# 1_Rotary_Encoder_Input_output.net
KiCad netlist of a schematic drawn in Altium Designer
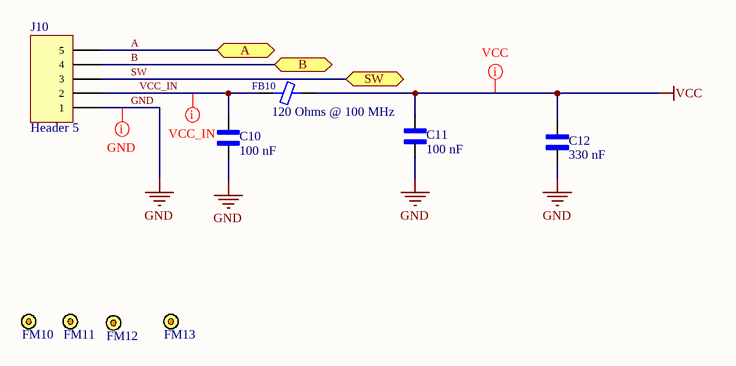
[diagram p0: 1_Rotary_Encoder_Input_output.SchDoc]

(export (version "E")
  (design (tool "Eeschema 10.0.6"))
  (components
    (comp (ref "C10")
      (value "100 nF")
      (footprint "C-0603")
      (description "Ceramic Capacitor 16V 0603 (1608 Metric)")
      (fields (field (name "MP") "C0603C104J4RAC") (field (name "MF") "KEMET"))
      (libsource (lib "Rotary_Encoder") (part "C-0603"))
    )
    (comp (ref "C11")
      (value "100 nF")
      (footprint "C-0603")
      (description "Ceramic Capacitor 16V 0603 (1608 Metric)")
      (fields (field (name "MP") "C0603C104J4RAC") (field (name "MF") "KEMET"))
      (libsource (lib "Rotary_Encoder") (part "C-0603"))
    )
    (comp (ref "C12")
      (value "330 nF")
      (footprint "C-0603")
      (description "Ceramic Capacitor 16V 0603 (1608 Metric)")
      (fields (field (name "MP") "C0603C104J4RAC") (field (name "MF") "KEMET"))
      (libsource (lib "Rotary_Encoder") (part "C-0603"))
    )
    (comp (ref "FB10")
      (value "120 Ohms @ 100 MHz")
      (footprint "FER 0603_1608")
      (description "FERRITE BEAD 120 OHM 0603 1LN")
      (fields
        (field (name "PART NUMBER") "PE-0603PFB121ST")
        (field (name "MANUFACTURER") "Pulse Electronics Network")
      )
      (libsource (lib "Rotary_Encoder") (part "Ferrite Chip"))
    )
    (comp (ref "FM10")
      (value "FM")
      (footprint "Fiducial_Marker_1mm")
      (description "Fiducial Marker")
      (libsource (lib "Rotary_Encoder") (part "Fiducial Marker"))
    )
    (comp (ref "FM11")
      (value "FM")
      (footprint "Fiducial_Marker_1mm")
      (description "Fiducial Marker")
      (libsource (lib "Rotary_Encoder") (part "Fiducial Marker"))
    )
    (comp (ref "FM12")
      (value "FM")
      (footprint "Fiducial_Marker_1mm")
      (description "Fiducial Marker")
      (libsource (lib "Rotary_Encoder") (part "Fiducial Marker"))
    )
    (comp (ref "FM13")
      (value "FM")
      (footprint "Fiducial_Marker_1mm")
      (description "Fiducial Marker")
      (libsource (lib "Rotary_Encoder") (part "Fiducial Marker"))
    )
    (comp (ref "J10")
      (value "Header 5")
      (footprint "HDR1X5")
      (description "Header, 5-Pin")
      (fields (field (name "PUBLISHER") "Altium Limited"))
      (libsource (lib "Rotary_Encoder") (part "Header 5"))
    )
  )
  (nets
    (net (code "1") (name "/A") (class "Default")
      (node (ref "J10") (pin "5") (pinfunction "5_5") (pintype "passive"))
    )
    (net (code "2") (name "/B") (class "Default")
      (node (ref "J10") (pin "4") (pinfunction "4_4") (pintype "passive"))
    )
    (net (code "3") (name "/SW") (class "Default")
      (node (ref "J10") (pin "3") (pinfunction "3_3") (pintype "passive"))
    )
    (net (code "4") (name "/VCC_IN") (class "Default")
      (node (ref "C10") (pin "2") (pinfunction "2_2") (pintype "passive"))
      (node (ref "FB10") (pin "1") (pinfunction "1_1") (pintype "passive"))
      (node (ref "J10") (pin "2") (pinfunction "2_2") (pintype "passive"))
    )
    (net (code "5") (name "GND") (class "Default")
      (node (ref "C10") (pin "1") (pinfunction "1_1") (pintype "passive"))
      (node (ref "C11") (pin "1") (pinfunction "1_1") (pintype "passive"))
      (node (ref "C12") (pin "1") (pinfunction "1_1") (pintype "passive"))
      (node (ref "J10") (pin "1") (pinfunction "1_1") (pintype "passive"))
    )
    (net (code "6") (name "VCC") (class "Default")
      (node (ref "C11") (pin "2") (pinfunction "2_2") (pintype "passive"))
      (node (ref "C12") (pin "2") (pinfunction "2_2") (pintype "passive"))
      (node (ref "FB10") (pin "2") (pinfunction "2_2") (pintype "passive"))
    )
  )
)
